# Z_Extruder_Motor_Drivers.net
KiCad netlist of a schematic drawn in Altium Designer
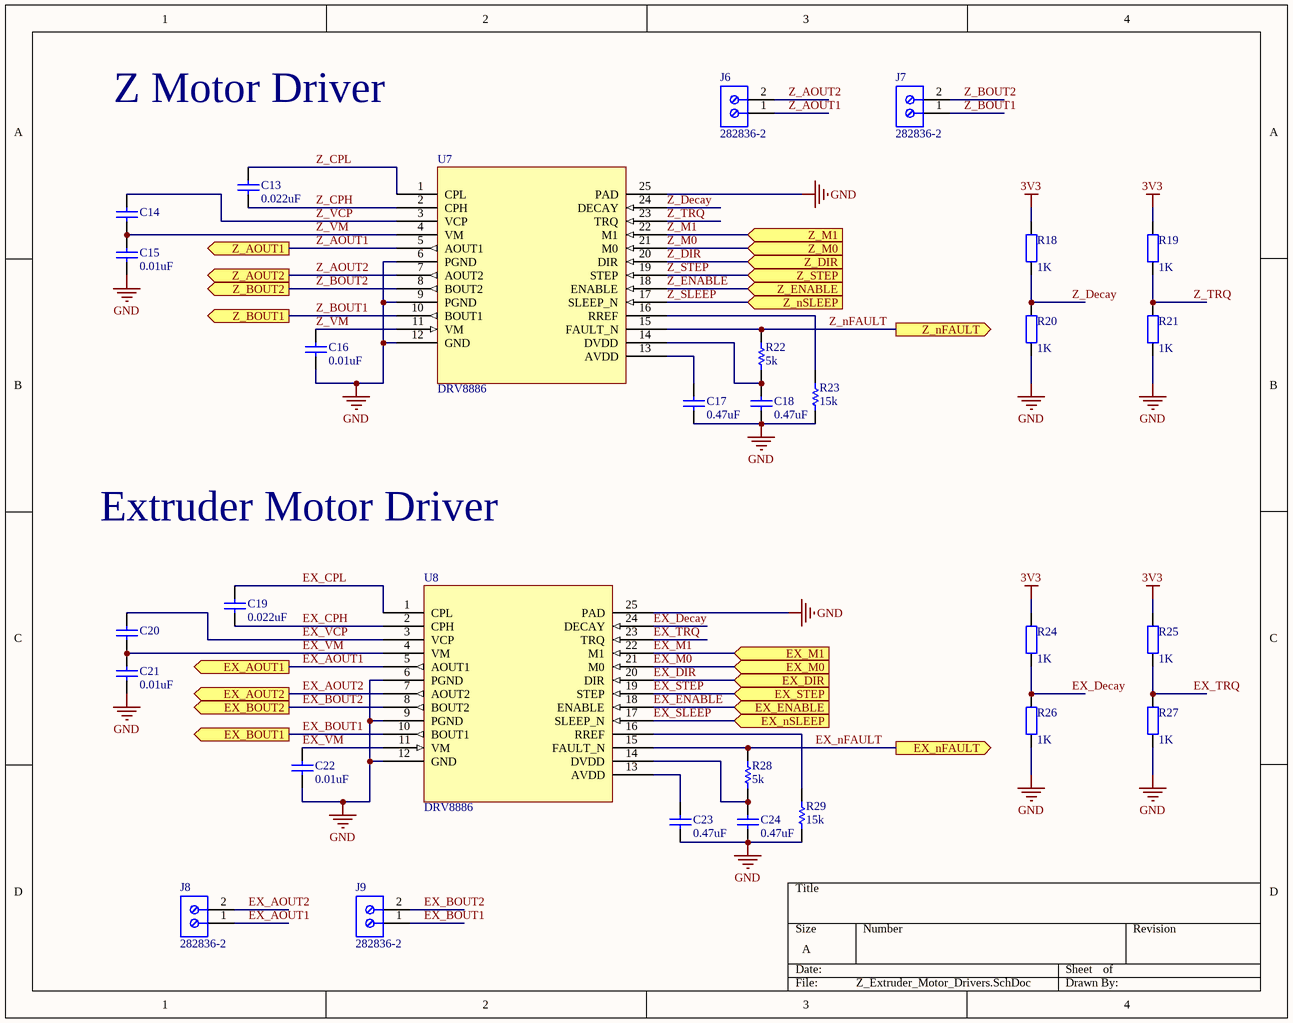
[diagram p0: Z_Extruder_Motor_Drivers.SchDoc]

(export (version "E")
  (design (tool "Eeschema 10.0.6"))
  (components
    (comp (ref "C13")
      (value "0.022uF")
      (footprint "CAPC1608X87X35ML15T15")
      (fields (field (name "PART NUMBER") "C0603C223K4RACTU") (field (name "MANUFACTURER") "Kemet"))
      (libsource (lib "Altium Content Vault") (part "CAP"))
    )
    (comp (ref "C14")
      (value "0.22uF")
      (footprint "TDK-C1608-2_A_M")
      (description "Cap Ceramic, 0.22 uF, +/- 10%, -55 to 125 degC, 2-Pin SMD (0603), RoHS, Tape and Reel")
      (fields (field (name "MANUFACTURER") "TDK") (field (name "TOLERANCE") "±10%"))
      (libsource (lib "Altium Content Vault") (part "CAP-NP-2"))
    )
    (comp (ref "C15")
      (value "0.01uF")
      (footprint "CAPC1608X87X35LL15T15")
      (fields (field (name "MANUFACTURER") "Kemet") (field (name "PART NUMBER") "C0603X103K5RACTU"))
      (libsource (lib "Altium Content Vault") (part "CAP"))
    )
    (comp (ref "C16")
      (value "0.01uF")
      (footprint "CAPC1608X87X35LL15T15")
      (fields (field (name "MANUFACTURER") "Kemet") (field (name "PART NUMBER") "C0603X103K5RACTU"))
      (libsource (lib "Altium Content Vault") (part "CAP"))
    )
    (comp (ref "C17")
      (value "0.47uF")
      (footprint "CAPC1608X90X35ML15T15")
      (fields
        (field (name "PART NUMBER") "06033C474KAT2A")
        (field (name "MANUFACTURER") "AVX Interconnect / Elco")
      )
      (libsource (lib "Altium Content Vault") (part "CAP"))
    )
    (comp (ref "C18")
      (value "0.47uF")
      (footprint "CAPC1608X90X35ML15T15")
      (fields
        (field (name "PART NUMBER") "06033C474KAT2A")
        (field (name "MANUFACTURER") "AVX Interconnect / Elco")
      )
      (libsource (lib "Altium Content Vault") (part "CAP"))
    )
    (comp (ref "C19")
      (value "0.022uF")
      (footprint "CAPC1608X87X35ML15T15")
      (fields (field (name "PART NUMBER") "C0603C223K4RACTU") (field (name "MANUFACTURER") "Kemet"))
      (libsource (lib "Altium Content Vault") (part "CAP"))
    )
    (comp (ref "C20")
      (value "0.22uF")
      (footprint "TDK-C1608-2_A_M")
      (description "Cap Ceramic, 0.22 uF, +/- 10%, -55 to 125 degC, 2-Pin SMD (0603), RoHS, Tape and Reel")
      (fields (field (name "MANUFACTURER") "TDK") (field (name "TOLERANCE") "±10%"))
      (libsource (lib "Altium Content Vault") (part "CAP-NP-2"))
    )
    (comp (ref "C21")
      (value "0.01uF")
      (footprint "CAPC1608X87X35LL15T15")
      (fields (field (name "MANUFACTURER") "Kemet") (field (name "PART NUMBER") "C0603X103K5RACTU"))
      (libsource (lib "Altium Content Vault") (part "CAP"))
    )
    (comp (ref "C22")
      (value "0.01uF")
      (footprint "CAPC1608X87X35LL15T15")
      (fields (field (name "MANUFACTURER") "Kemet") (field (name "PART NUMBER") "C0603X103K5RACTU"))
      (libsource (lib "Altium Content Vault") (part "CAP"))
    )
    (comp (ref "C23")
      (value "0.47uF")
      (footprint "CAPC1608X90X35ML15T15")
      (fields
        (field (name "PART NUMBER") "06033C474KAT2A")
        (field (name "MANUFACTURER") "AVX Interconnect / Elco")
      )
      (libsource (lib "Altium Content Vault") (part "CAP"))
    )
    (comp (ref "C24")
      (value "0.47uF")
      (footprint "CAPC1608X90X35ML15T15")
      (fields
        (field (name "PART NUMBER") "06033C474KAT2A")
        (field (name "MANUFACTURER") "AVX Interconnect / Elco")
      )
      (libsource (lib "Altium Content Vault") (part "CAP"))
    )
    (comp (ref "J6")
      (value "282836-2")
      (footprint "TECO-282836-2_V")
      (description "Female Header, Pitch 5 mm, 1 x 2 Position, Height 10 mm, Tail Length 3.5 mm, Rohs, Bulk")
      (fields (field (name "VOLTAGE") "300V") (field (name "MANUFACTURER") "TE Connectivity"))
      (libsource (lib "Altium Content Vault") (part "CN-1P-F-TB2"))
    )
    (comp (ref "J7")
      (value "282836-2")
      (footprint "TECO-282836-2_V")
      (description "Female Header, Pitch 5 mm, 1 x 2 Position, Height 10 mm, Tail Length 3.5 mm, Rohs, Bulk")
      (fields (field (name "VOLTAGE") "300V") (field (name "MANUFACTURER") "TE Connectivity"))
      (libsource (lib "Altium Content Vault") (part "CN-1P-F-TB2"))
    )
    (comp (ref "J8")
      (value "282836-2")
      (footprint "TECO-282836-2_V")
      (description "Female Header, Pitch 5 mm, 1 x 2 Position, Height 10 mm, Tail Length 3.5 mm, Rohs, Bulk")
      (fields (field (name "VOLTAGE") "300V") (field (name "MANUFACTURER") "TE Connectivity"))
      (libsource (lib "Altium Content Vault") (part "CN-1P-F-TB2"))
    )
    (comp (ref "J9")
      (value "282836-2")
      (footprint "TECO-282836-2_V")
      (description "Female Header, Pitch 5 mm, 1 x 2 Position, Height 10 mm, Tail Length 3.5 mm, Rohs, Bulk")
      (fields (field (name "VOLTAGE") "300V") (field (name "MANUFACTURER") "TE Connectivity"))
      (libsource (lib "Altium Content Vault") (part "CN-1P-F-TB2"))
    )
    (comp (ref "R18")
      (value "1K")
      (footprint "AXIAL-0.4")
      (description "Resistor")
      (fields (field (name "Comment") "?") (field (name "PUBLISHER") "Altium Limited"))
      (libsource (lib "Miscellaneous Devices") (part "Res2"))
    )
    (comp (ref "R19")
      (value "1K")
      (footprint "AXIAL-0.4")
      (description "Resistor")
      (fields (field (name "Comment") "?") (field (name "PUBLISHER") "Altium Limited"))
      (libsource (lib "Miscellaneous Devices") (part "Res2"))
    )
    (comp (ref "R20")
      (value "1K")
      (footprint "AXIAL-0.4")
      (description "Resistor")
      (fields (field (name "Comment") "Res2") (field (name "PUBLISHER") "Altium Limited"))
      (libsource (lib "Miscellaneous Devices") (part "Res2"))
    )
    (comp (ref "R21")
      (value "1K")
      (footprint "AXIAL-0.4")
      (description "Resistor")
      (fields (field (name "Comment") "Res2") (field (name "PUBLISHER") "Altium Limited"))
      (libsource (lib "Miscellaneous Devices") (part "Res2"))
    )
    (comp (ref "R22")
      (value "5k")
      (footprint "RESC1608X55X25ML10T15")
      (description "Chip Resistor, 0 Ohm, +/- 5%, 0.1 W, -55 to 155 degC, 0603 (1608 Metric), RoHS, Tape and Reel")
      (fields (field (name "TOLERANCE") "5%") (field (name "MANUFACTURER") "Yageo"))
      (libsource (lib "Altium Content Vault") (part "RES-2"))
    )
    (comp (ref "R23")
      (value "15k")
      (footprint "RESC1608X55X25ML10T15")
      (description "Chip Resistor, 0 Ohm, +/- 5%, 0.1 W, -55 to 155 degC, 0603 (1608 Metric), RoHS, Tape and Reel")
      (fields (field (name "TOLERANCE") "5%") (field (name "MANUFACTURER") "Yageo"))
      (libsource (lib "Altium Content Vault") (part "RES-2"))
    )
    (comp (ref "R24")
      (value "1K")
      (footprint "AXIAL-0.4")
      (description "Resistor")
      (fields (field (name "Comment") "?") (field (name "PUBLISHER") "Altium Limited"))
      (libsource (lib "Miscellaneous Devices") (part "Res2"))
    )
    (comp (ref "R25")
      (value "1K")
      (footprint "AXIAL-0.4")
      (description "Resistor")
      (fields (field (name "Comment") "?") (field (name "PUBLISHER") "Altium Limited"))
      (libsource (lib "Miscellaneous Devices") (part "Res2"))
    )
    (comp (ref "R26")
      (value "1K")
      (footprint "AXIAL-0.4")
      (description "Resistor")
      (fields (field (name "Comment") "Res2") (field (name "PUBLISHER") "Altium Limited"))
      (libsource (lib "Miscellaneous Devices") (part "Res2"))
    )
    (comp (ref "R27")
      (value "1K")
      (footprint "AXIAL-0.4")
      (description "Resistor")
      (fields (field (name "Comment") "Res2") (field (name "PUBLISHER") "Altium Limited"))
      (libsource (lib "Miscellaneous Devices") (part "Res2"))
    )
    (comp (ref "R28")
      (value "5k")
      (footprint "RESC1608X55X25ML10T15")
      (description "Chip Resistor, 0 Ohm, +/- 5%, 0.1 W, -55 to 155 degC, 0603 (1608 Metric), RoHS, Tape and Reel")
      (fields (field (name "TOLERANCE") "5%") (field (name "MANUFACTURER") "Yageo"))
      (libsource (lib "Altium Content Vault") (part "RES-2"))
    )
    (comp (ref "R29")
      (value "15k")
      (footprint "RESC1608X55X25ML10T15")
      (description "Chip Resistor, 0 Ohm, +/- 5%, 0.1 W, -55 to 155 degC, 0603 (1608 Metric), RoHS, Tape and Reel")
      (fields (field (name "TOLERANCE") "5%") (field (name "MANUFACTURER") "Yageo"))
      (libsource (lib "Altium Content Vault") (part "RES-2"))
    )
    (comp (ref "U7")
      (value "DRV8886")
      (footprint "PWP0024B_N")
      (libsource (lib "TI_DRV8886") (part "DRV8886"))
    )
    (comp (ref "U8")
      (value "DRV8886")
      (footprint "PWP0024B_N")
      (libsource (lib "TI_DRV8886") (part "DRV8886"))
    )
  )
  (nets
    (net (code "1") (name "/EX_AOUT1") (class "Default")
      (node (ref "J8") (pin "1") (pinfunction "1_1") (pintype "passive"))
      (node (ref "U8") (pin "5") (pinfunction "AOUT1_5") (pintype "output"))
    )
    (net (code "2") (name "/EX_AOUT2") (class "Default")
      (node (ref "J8") (pin "2") (pinfunction "2_2") (pintype "passive"))
      (node (ref "U8") (pin "7") (pinfunction "AOUT2_7") (pintype "output"))
    )
    (net (code "3") (name "/EX_BOUT1") (class "Default")
      (node (ref "J9") (pin "1") (pinfunction "1_1") (pintype "passive"))
      (node (ref "U8") (pin "10") (pinfunction "BOUT1_10") (pintype "output"))
    )
    (net (code "4") (name "/EX_BOUT2") (class "Default")
      (node (ref "J9") (pin "2") (pinfunction "2_2") (pintype "passive"))
      (node (ref "U8") (pin "8") (pinfunction "BOUT2_8") (pintype "output"))
    )
    (net (code "5") (name "/EX_CPH") (class "Default")
      (node (ref "C19") (pin "1") (pinfunction "1_1") (pintype "passive"))
      (node (ref "U8") (pin "2") (pinfunction "CPH_2") (pintype "passive"))
    )
    (net (code "6") (name "/EX_CPL") (class "Default")
      (node (ref "C19") (pin "2") (pinfunction "2_2") (pintype "passive"))
      (node (ref "U8") (pin "1") (pinfunction "CPL_1") (pintype "passive"))
    )
    (net (code "7") (name "/EX_DIR") (class "Default")
      (node (ref "U8") (pin "20") (pinfunction "DIR_20") (pintype "input"))
    )
    (net (code "8") (name "/EX_Decay") (class "Default")
      (node (ref "R24") (pin "1") (pinfunction "1_1") (pintype "passive"))
      (node (ref "R26") (pin "2") (pinfunction "2_2") (pintype "passive"))
      (node (ref "U8") (pin "24") (pinfunction "DECAY_24") (pintype "input"))
    )
    (net (code "9") (name "/EX_ENABLE") (class "Default")
      (node (ref "U8") (pin "18") (pinfunction "ENABLE_18") (pintype "input"))
    )
    (net (code "10") (name "/EX_M0") (class "Default")
      (node (ref "U8") (pin "21") (pinfunction "M0_21") (pintype "input"))
    )
    (net (code "11") (name "/EX_M1") (class "Default")
      (node (ref "U8") (pin "22") (pinfunction "M1_22") (pintype "input"))
    )
    (net (code "12") (name "/EX_STEP") (class "Default")
      (node (ref "U8") (pin "19") (pinfunction "STEP_19") (pintype "input"))
    )
    (net (code "13") (name "/EX_TRQ") (class "Default")
      (node (ref "R25") (pin "1") (pinfunction "1_1") (pintype "passive"))
      (node (ref "R27") (pin "2") (pinfunction "2_2") (pintype "passive"))
      (node (ref "U8") (pin "23") (pinfunction "TRQ_23") (pintype "input"))
    )
    (net (code "14") (name "/EX_VCP") (class "Default")
      (node (ref "C20") (pin "2") (pinfunction "2_2") (pintype "passive"))
      (node (ref "U8") (pin "3") (pinfunction "VCP_3") (pintype "passive"))
    )
    (net (code "15") (name "/EX_VM") (class "Default")
      (node (ref "C20") (pin "1") (pinfunction "1_1") (pintype "passive"))
      (node (ref "C21") (pin "1") (pinfunction "1_1") (pintype "passive"))
      (node (ref "C22") (pin "1") (pinfunction "1_1") (pintype "passive"))
      (node (ref "U8") (pin "11") (pinfunction "VM_11") (pintype "input"))
      (node (ref "U8") (pin "4") (pinfunction "VM_4") (pintype "passive"))
    )
    (net (code "16") (name "/EX_nFAULT") (class "Default")
      (node (ref "R28") (pin "2") (pinfunction "2_2") (pintype "passive"))
      (node (ref "U8") (pin "15") (pinfunction "FAULT_N_15") (pintype "passive"))
    )
    (net (code "17") (name "/EX~{_}SLEEP") (class "Default")
      (node (ref "U8") (pin "17") (pinfunction "SLEEP_N_17") (pintype "input"))
    )
    (net (code "18") (name "/Z_AOUT1") (class "Default")
      (node (ref "J6") (pin "1") (pinfunction "1_1") (pintype "passive"))
      (node (ref "U7") (pin "5") (pinfunction "AOUT1_5") (pintype "output"))
    )
    (net (code "19") (name "/Z_AOUT2") (class "Default")
      (node (ref "J6") (pin "2") (pinfunction "2_2") (pintype "passive"))
      (node (ref "U7") (pin "7") (pinfunction "AOUT2_7") (pintype "output"))
    )
    (net (code "20") (name "/Z_BOUT1") (class "Default")
      (node (ref "J7") (pin "1") (pinfunction "1_1") (pintype "passive"))
      (node (ref "U7") (pin "10") (pinfunction "BOUT1_10") (pintype "output"))
    )
    (net (code "21") (name "/Z_BOUT2") (class "Default")
      (node (ref "J7") (pin "2") (pinfunction "2_2") (pintype "passive"))
      (node (ref "U7") (pin "8") (pinfunction "BOUT2_8") (pintype "output"))
    )
    (net (code "22") (name "/Z_CPH") (class "Default")
      (node (ref "C13") (pin "1") (pinfunction "1_1") (pintype "passive"))
      (node (ref "U7") (pin "2") (pinfunction "CPH_2") (pintype "passive"))
    )
    (net (code "23") (name "/Z_CPL") (class "Default")
      (node (ref "C13") (pin "2") (pinfunction "2_2") (pintype "passive"))
      (node (ref "U7") (pin "1") (pinfunction "CPL_1") (pintype "passive"))
    )
    (net (code "24") (name "/Z_DIR") (class "Default")
      (node (ref "U7") (pin "20") (pinfunction "DIR_20") (pintype "input"))
    )
    (net (code "25") (name "/Z_Decay") (class "Default")
      (node (ref "R18") (pin "1") (pinfunction "1_1") (pintype "passive"))
      (node (ref "R20") (pin "2") (pinfunction "2_2") (pintype "passive"))
      (node (ref "U7") (pin "24") (pinfunction "DECAY_24") (pintype "input"))
    )
    (net (code "26") (name "/Z_ENABLE") (class "Default")
      (node (ref "U7") (pin "18") (pinfunction "ENABLE_18") (pintype "input"))
    )
    (net (code "27") (name "/Z_M0") (class "Default")
      (node (ref "U7") (pin "21") (pinfunction "M0_21") (pintype "input"))
    )
    (net (code "28") (name "/Z_M1") (class "Default")
      (node (ref "U7") (pin "22") (pinfunction "M1_22") (pintype "input"))
    )
    (net (code "29") (name "/Z_STEP") (class "Default")
      (node (ref "U7") (pin "19") (pinfunction "STEP_19") (pintype "input"))
    )
    (net (code "30") (name "/Z_TRQ") (class "Default")
      (node (ref "R19") (pin "1") (pinfunction "1_1") (pintype "passive"))
      (node (ref "R21") (pin "2") (pinfunction "2_2") (pintype "passive"))
      (node (ref "U7") (pin "23") (pinfunction "TRQ_23") (pintype "input"))
    )
    (net (code "31") (name "/Z_VCP") (class "Default")
      (node (ref "C14") (pin "2") (pinfunction "2_2") (pintype "passive"))
      (node (ref "U7") (pin "3") (pinfunction "VCP_3") (pintype "passive"))
    )
    (net (code "32") (name "/Z_VM") (class "Default")
      (node (ref "C14") (pin "1") (pinfunction "1_1") (pintype "passive"))
      (node (ref "C15") (pin "1") (pinfunction "1_1") (pintype "passive"))
      (node (ref "C16") (pin "1") (pinfunction "1_1") (pintype "passive"))
      (node (ref "U7") (pin "11") (pinfunction "VM_11") (pintype "input"))
      (node (ref "U7") (pin "4") (pinfunction "VM_4") (pintype "passive"))
    )
    (net (code "33") (name "/Z_nFAULT") (class "Default")
      (node (ref "R22") (pin "2") (pinfunction "2_2") (pintype "passive"))
      (node (ref "U7") (pin "15") (pinfunction "FAULT_N_15") (pintype "passive"))
    )
    (net (code "34") (name "/Z~{_}SLEEP") (class "Default")
      (node (ref "U7") (pin "17") (pinfunction "SLEEP_N_17") (pintype "input"))
    )
    (net (code "35") (name "3V3") (class "Default")
      (node (ref "R18") (pin "2") (pinfunction "2_2") (pintype "passive"))
      (node (ref "R19") (pin "2") (pinfunction "2_2") (pintype "passive"))
      (node (ref "R24") (pin "2") (pinfunction "2_2") (pintype "passive"))
      (node (ref "R25") (pin "2") (pinfunction "2_2") (pintype "passive"))
    )
    (net (code "36") (name "GND") (class "Default")
      (node (ref "C15") (pin "2") (pinfunction "2_2") (pintype "passive"))
      (node (ref "C16") (pin "2") (pinfunction "2_2") (pintype "passive"))
      (node (ref "C17") (pin "1") (pinfunction "1_1") (pintype "passive"))
      (node (ref "C18") (pin "1") (pinfunction "1_1") (pintype "passive"))
      (node (ref "C21") (pin "2") (pinfunction "2_2") (pintype "passive"))
      (node (ref "C22") (pin "2") (pinfunction "2_2") (pintype "passive"))
      (node (ref "C23") (pin "1") (pinfunction "1_1") (pintype "passive"))
      (node (ref "C24") (pin "1") (pinfunction "1_1") (pintype "passive"))
      (node (ref "R20") (pin "1") (pinfunction "1_1") (pintype "passive"))
      (node (ref "R21") (pin "1") (pinfunction "1_1") (pintype "passive"))
      (node (ref "R23") (pin "1") (pinfunction "1_1") (pintype "passive"))
      (node (ref "R26") (pin "1") (pinfunction "1_1") (pintype "passive"))
      (node (ref "R27") (pin "1") (pinfunction "1_1") (pintype "passive"))
      (node (ref "R29") (pin "1") (pinfunction "1_1") (pintype "passive"))
      (node (ref "U7") (pin "12") (pinfunction "GND_12") (pintype "passive"))
      (node (ref "U7") (pin "25") (pinfunction "PAD_25") (pintype "passive"))
      (node (ref "U7") (pin "6") (pinfunction "PGND_6") (pintype "passive"))
      (node (ref "U7") (pin "9") (pinfunction "PGND_9") (pintype "passive"))
      (node (ref "U8") (pin "12") (pinfunction "GND_12") (pintype "passive"))
      (node (ref "U8") (pin "25") (pinfunction "PAD_25") (pintype "passive"))
      (node (ref "U8") (pin "6") (pinfunction "PGND_6") (pintype "passive"))
      (node (ref "U8") (pin "9") (pinfunction "PGND_9") (pintype "passive"))
    )
    (net (code "37") (name "Net-(U7-AVDD)") (class "Default")
      (node (ref "C17") (pin "2") (pinfunction "2_2") (pintype "passive"))
      (node (ref "U7") (pin "13") (pinfunction "AVDD_13") (pintype "passive"))
    )
    (net (code "38") (name "Net-(U7-DVDD)") (class "Default")
      (node (ref "C18") (pin "2") (pinfunction "2_2") (pintype "passive"))
      (node (ref "R22") (pin "1") (pinfunction "1_1") (pintype "passive"))
      (node (ref "U7") (pin "14") (pinfunction "DVDD_14") (pintype "passive"))
    )
    (net (code "39") (name "Net-(U7-RREF)") (class "Default")
      (node (ref "R23") (pin "2") (pinfunction "2_2") (pintype "passive"))
      (node (ref "U7") (pin "16") (pinfunction "RREF_16") (pintype "passive"))
    )
    (net (code "40") (name "Net-(U8-AVDD)") (class "Default")
      (node (ref "C23") (pin "2") (pinfunction "2_2") (pintype "passive"))
      (node (ref "U8") (pin "13") (pinfunction "AVDD_13") (pintype "passive"))
    )
    (net (code "41") (name "Net-(U8-DVDD)") (class "Default")
      (node (ref "C24") (pin "2") (pinfunction "2_2") (pintype "passive"))
      (node (ref "R28") (pin "1") (pinfunction "1_1") (pintype "passive"))
      (node (ref "U8") (pin "14") (pinfunction "DVDD_14") (pintype "passive"))
    )
    (net (code "42") (name "Net-(U8-RREF)") (class "Default")
      (node (ref "R29") (pin "2") (pinfunction "2_2") (pintype "passive"))
      (node (ref "U8") (pin "16") (pinfunction "RREF_16") (pintype "passive"))
    )
  )
)
